# 02_MCU.net
KiCad netlist of a schematic drawn in Altium Designer
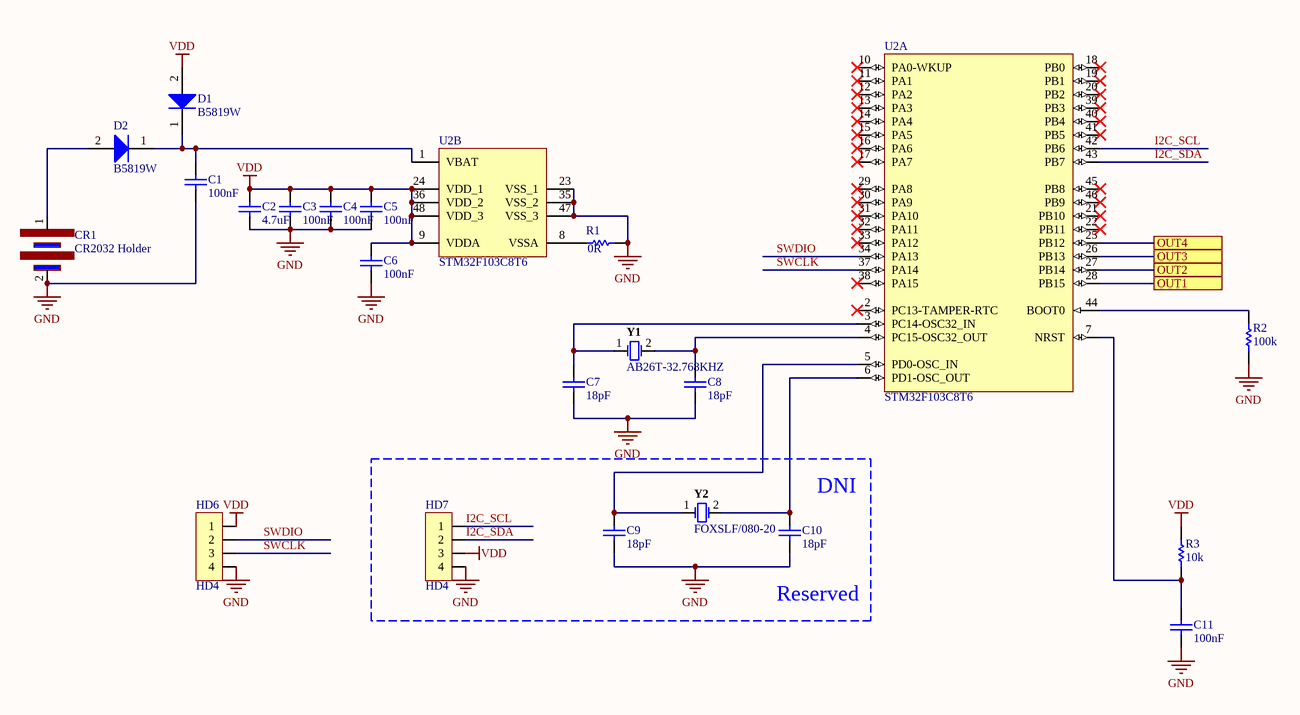
[diagram p0: 02. MCU.SchDoc]

(export (version "E")
  (design (tool "Eeschema 10.0.6"))
  (components
    (comp (ref "C1")
      (value "100nF")
      (footprint "0603 CAP")
      (description "Chip Capacitor, 0.1 uF, +/- 10%, 50 V, -55 to 125 degC, 0603 (1608 Metric), RoHS, Tape and Reel")
      (fields (field (name "TOLERANCE") "10%") (field (name "VOLTAGE") "50V"))
      (libsource (lib "SyTungNguyen") (part "CAP-NP-2"))
    )
    (comp (ref "C2")
      (value "4.7uF")
      (footprint "0603 CAP")
      (description "Chip Capacitor, 0.1 uF, +/- 10%, 50 V, -55 to 125 degC, 0603 (1608 Metric), RoHS, Tape and Reel")
      (fields (field (name "TOLERANCE") "10%") (field (name "VOLTAGE") "50V"))
      (libsource (lib "SyTungNguyen") (part "CAP-NP-2"))
    )
    (comp (ref "C3")
      (value "100nF")
      (footprint "0603 CAP")
      (description "Chip Capacitor, 0.1 uF, +/- 10%, 50 V, -55 to 125 degC, 0603 (1608 Metric), RoHS, Tape and Reel")
      (fields (field (name "TOLERANCE") "10%") (field (name "VOLTAGE") "50V"))
      (libsource (lib "SyTungNguyen") (part "CAP-NP-2"))
    )
    (comp (ref "C4")
      (value "100nF")
      (footprint "0603 CAP")
      (description "Chip Capacitor, 0.1 uF, +/- 10%, 50 V, -55 to 125 degC, 0603 (1608 Metric), RoHS, Tape and Reel")
      (fields (field (name "TOLERANCE") "10%") (field (name "VOLTAGE") "50V"))
      (libsource (lib "SyTungNguyen") (part "CAP-NP-2"))
    )
    (comp (ref "C5")
      (value "100nF")
      (footprint "0603 CAP")
      (description "Chip Capacitor, 0.1 uF, +/- 10%, 50 V, -55 to 125 degC, 0603 (1608 Metric), RoHS, Tape and Reel")
      (fields (field (name "TOLERANCE") "10%") (field (name "VOLTAGE") "50V"))
      (libsource (lib "SyTungNguyen") (part "CAP-NP-2"))
    )
    (comp (ref "C6")
      (value "100nF")
      (footprint "0603 CAP")
      (description "Chip Capacitor, 0.1 uF, +/- 10%, 50 V, -55 to 125 degC, 0603 (1608 Metric), RoHS, Tape and Reel")
      (fields (field (name "TOLERANCE") "10%") (field (name "VOLTAGE") "50V"))
      (libsource (lib "SyTungNguyen") (part "CAP-NP-2"))
    )
    (comp (ref "C7")
      (value "18pF")
      (footprint "0603 CAP")
      (description "Chip Capacitor, 18 pF, +/- 5%, 50 V, -55 to 125 degC, 0603 (1608 Metric), RoHS, Tape and Reel")
      (fields (field (name "MANUFACTURER") "Samsung Electro-Mechanics"))
      (libsource (lib "SyTungNguyen") (part "CAP-NP-2"))
    )
    (comp (ref "C8")
      (value "18pF")
      (footprint "0603 CAP")
      (description "Chip Capacitor, 18 pF, +/- 5%, 50 V, -55 to 125 degC, 0603 (1608 Metric), RoHS, Tape and Reel")
      (fields (field (name "MANUFACTURER") "Samsung Electro-Mechanics"))
      (libsource (lib "SyTungNguyen") (part "CAP-NP-2"))
    )
    (comp (ref "C9")
      (value "18pF")
      (footprint "0603 CAP")
      (description "Chip Capacitor, 18 pF, +/- 5%, 50 V, -55 to 125 degC, 0603 (1608 Metric), RoHS, Tape and Reel")
      (fields (field (name "MANUFACTURER") "Samsung Electro-Mechanics"))
      (libsource (lib "SyTungNguyen") (part "CAP-NP-2"))
    )
    (comp (ref "C10")
      (value "18pF")
      (footprint "0603 CAP")
      (description "Chip Capacitor, 18 pF, +/- 5%, 50 V, -55 to 125 degC, 0603 (1608 Metric), RoHS, Tape and Reel")
      (fields (field (name "MANUFACTURER") "Samsung Electro-Mechanics"))
      (libsource (lib "SyTungNguyen") (part "CAP-NP-2"))
    )
    (comp (ref "C11")
      (value "100nF")
      (footprint "0603 CAP")
      (description "Chip Capacitor, 0.1 uF, +/- 10%, 50 V, -55 to 125 degC, 0603 (1608 Metric), RoHS, Tape and Reel")
      (fields (field (name "TOLERANCE") "10%") (field (name "VOLTAGE") "50V"))
      (libsource (lib "SyTungNguyen") (part "CAP-NP-2"))
    )
    (comp (ref "CR1")
      (value "CR2032 Holder")
      (footprint "CR2032")
      (libsource (lib "SyTungNguyen") (part "CR2032"))
    )
    (comp (ref "D1")
      (value "B5819W")
      (footprint "SOD123")
      (description "Switching Diode, 2-Pin SOD-323, Pb-Free, Tape and Reel")
      (fields (field (name "MANUFACTURER") "On Semiconductor") (field (name "PARTNUMBER") "BAS16HT1G"))
      (libsource (lib "SyTungNguyen") (part "ONSC-D-K1A2-2"))
    )
    (comp (ref "D2")
      (value "B5819W")
      (footprint "SOD123")
      (description "Switching Diode, 2-Pin SOD-323, Pb-Free, Tape and Reel")
      (fields (field (name "MANUFACTURER") "On Semiconductor") (field (name "PARTNUMBER") "BAS16HT1G"))
      (libsource (lib "SyTungNguyen") (part "ONSC-D-K1A2-2"))
    )
    (comp (ref "HD6")
      (value "HD4")
      (footprint "HD4x1 2.54mm")
      (libsource (lib "SyTungNguyen") (part "HD4x1"))
    )
    (comp (ref "HD7")
      (value "HD4")
      (footprint "HD4x1 2.54mm")
      (libsource (lib "SyTungNguyen") (part "HD4x1"))
    )
    (comp (ref "R1")
      (value "0R")
      (footprint "0603 RES")
      (fields (field (name "MANUFACTURER") "Vishay Dale") (field (name "PART NUMBER") "CRCW06030000Z0EB"))
      (libsource (lib "SyTungNguyen") (part "RES"))
    )
    (comp (ref "R2")
      (value "100k")
      (footprint "0603 RES")
      (fields (field (name "MANUFACTURER") "Vishay Dale") (field (name "PART NUMBER") "CRCW06030000Z0EB"))
      (libsource (lib "SyTungNguyen") (part "RES"))
    )
    (comp (ref "R3")
      (value "10k")
      (footprint "0603 RES")
      (fields (field (name "MANUFACTURER") "Vishay Dale") (field (name "PART NUMBER") "CRCW06030000Z0EB"))
      (libsource (lib "SyTungNguyen") (part "RES"))
    )
    (comp (ref "U2")
      (value "STM32F103C8T6")
      (footprint "STM-LQFP48")
      (libsource (lib "SyTungNguyen") (part "MC-ARM-STM32F103X8_B-SQ48"))
    )
    (comp (ref "Y1")
      (value "AB26T-32.768KHZ")
      (footprint "Crystal 3x8")
      (description "Crystal, 12.5 pF, 32.768 KHz, -10 to 60 degC, 2-Pin THD, RoHS, Bulk")
      (fields (field (name "MANUFACTURER") "ABRACON") (field (name "TOLERANCE") "20PPM"))
      (libsource (lib "SyTungNguyen") (part "XTAL-1-2-2"))
    )
    (comp (ref "Y2")
      (value "FOXSLF/080-20")
      (footprint "CRYSTAL HC49")
      (description "Resistance Weld Thru-Hole Crystal, 8 MHz, -20 to 70 degC, 2-Pin THD, RoHS, Bulk")
      (libsource (lib "SyTungNguyen") (part "XTAL-1-2-2"))
    )
  )
  (nets
    (net (code "1") (name "/I2C_SCL") (class "Default")
      (node (ref "HD7") (pin "1") (pinfunction "1_1") (pintype "passive"))
      (node (ref "U2") (pin "42") (pinfunction "PB6_42") (pintype "bidirectional"))
    )
    (net (code "2") (name "/I2C_SDA") (class "Default")
      (node (ref "HD7") (pin "2") (pinfunction "2_2") (pintype "passive"))
      (node (ref "U2") (pin "43") (pinfunction "PB7_43") (pintype "bidirectional"))
    )
    (net (code "3") (name "/OUT1") (class "Default")
      (node (ref "U2") (pin "28") (pinfunction "PB15_28") (pintype "bidirectional"))
    )
    (net (code "4") (name "/OUT2") (class "Default")
      (node (ref "U2") (pin "27") (pinfunction "PB14_27") (pintype "bidirectional"))
    )
    (net (code "5") (name "/OUT3") (class "Default")
      (node (ref "U2") (pin "26") (pinfunction "PB13_26") (pintype "bidirectional"))
    )
    (net (code "6") (name "/OUT4") (class "Default")
      (node (ref "U2") (pin "25") (pinfunction "PB12_25") (pintype "bidirectional"))
    )
    (net (code "7") (name "/SWCLK") (class "Default")
      (node (ref "HD6") (pin "3") (pinfunction "3_3") (pintype "passive"))
      (node (ref "U2") (pin "37") (pinfunction "PA14_37") (pintype "bidirectional"))
    )
    (net (code "8") (name "/SWDIO") (class "Default")
      (node (ref "HD6") (pin "2") (pinfunction "2_2") (pintype "passive"))
      (node (ref "U2") (pin "34") (pinfunction "PA13_34") (pintype "bidirectional"))
    )
    (net (code "9") (name "GND") (class "Default")
      (node (ref "C1") (pin "1") (pinfunction "1_1") (pintype "passive"))
      (node (ref "C10") (pin "1") (pinfunction "1_1") (pintype "passive"))
      (node (ref "C11") (pin "1") (pinfunction "1_1") (pintype "passive"))
      (node (ref "C2") (pin "1") (pinfunction "1_1") (pintype "passive"))
      (node (ref "C3") (pin "1") (pinfunction "1_1") (pintype "passive"))
      (node (ref "C4") (pin "1") (pinfunction "1_1") (pintype "passive"))
      (node (ref "C5") (pin "1") (pinfunction "1_1") (pintype "passive"))
      (node (ref "C6") (pin "1") (pinfunction "1_1") (pintype "passive"))
      (node (ref "C7") (pin "1") (pinfunction "1_1") (pintype "passive"))
      (node (ref "C8") (pin "1") (pinfunction "1_1") (pintype "passive"))
      (node (ref "C9") (pin "1") (pinfunction "1_1") (pintype "passive"))
      (node (ref "CR1") (pin "2") (pinfunction "VSS_2") (pintype "passive"))
      (node (ref "HD6") (pin "4") (pinfunction "4_4") (pintype "passive"))
      (node (ref "HD7") (pin "4") (pinfunction "4_4") (pintype "passive"))
      (node (ref "R1") (pin "2") (pinfunction "2_2") (pintype "passive"))
      (node (ref "R2") (pin "1") (pinfunction "1_1") (pintype "passive"))
      (node (ref "U2") (pin "23") (pinfunction "VSS_1_23") (pintype "power_in"))
      (node (ref "U2") (pin "35") (pinfunction "VSS_2_35") (pintype "power_in"))
      (node (ref "U2") (pin "47") (pinfunction "VSS_3_47") (pintype "power_in"))
    )
    (net (code "10") (name "Net-(CR1-VBAT)") (class "Default")
      (node (ref "CR1") (pin "1") (pinfunction "VBAT_1") (pintype "passive"))
      (node (ref "D2") (pin "2") (pinfunction "A_2") (pintype "passive"))
    )
    (net (code "11") (name "Net-(D1-K)") (class "Default")
      (node (ref "C1") (pin "2") (pinfunction "2_2") (pintype "passive"))
      (node (ref "D1") (pin "1") (pinfunction "K_1") (pintype "passive"))
      (node (ref "D2") (pin "1") (pinfunction "K_1") (pintype "passive"))
      (node (ref "U2") (pin "1") (pinfunction "VBAT_1") (pintype "power_in"))
    )
    (net (code "12") (name "Net-(U2A-BOOT0)") (class "Default")
      (node (ref "R2") (pin "2") (pinfunction "2_2") (pintype "passive"))
      (node (ref "U2") (pin "44") (pinfunction "BOOT0_44") (pintype "input"))
    )
    (net (code "13") (name "Net-(U2A-NRST)") (class "Default")
      (node (ref "C11") (pin "2") (pinfunction "2_2") (pintype "passive"))
      (node (ref "R3") (pin "1") (pinfunction "1_1") (pintype "passive"))
      (node (ref "U2") (pin "7") (pinfunction "NRST_7") (pintype "bidirectional"))
    )
    (net (code "14") (name "Net-(U2A-PC14-OSC32_IN)") (class "Default")
      (node (ref "C7") (pin "2") (pinfunction "2_2") (pintype "passive"))
      (node (ref "U2") (pin "3") (pinfunction "PC14-OSC32_IN_3") (pintype "bidirectional"))
      (node (ref "Y1") (pin "1") (pinfunction "1_1") (pintype "passive"))
    )
    (net (code "15") (name "Net-(U2A-PC15-OSC32_OUT)") (class "Default")
      (node (ref "C8") (pin "2") (pinfunction "2_2") (pintype "passive"))
      (node (ref "U2") (pin "4") (pinfunction "PC15-OSC32_OUT_4") (pintype "bidirectional"))
      (node (ref "Y1") (pin "2") (pinfunction "2_2") (pintype "passive"))
    )
    (net (code "16") (name "Net-(U2A-PD0-OSC_IN)") (class "Default")
      (node (ref "C9") (pin "2") (pinfunction "2_2") (pintype "passive"))
      (node (ref "U2") (pin "5") (pinfunction "PD0-OSC_IN_5") (pintype "bidirectional"))
      (node (ref "Y2") (pin "1") (pinfunction "1_1") (pintype "passive"))
    )
    (net (code "17") (name "Net-(U2A-PD1-OSC_OUT)") (class "Default")
      (node (ref "C10") (pin "2") (pinfunction "2_2") (pintype "passive"))
      (node (ref "U2") (pin "6") (pinfunction "PD1-OSC_OUT_6") (pintype "bidirectional"))
      (node (ref "Y2") (pin "2") (pinfunction "2_2") (pintype "passive"))
    )
    (net (code "18") (name "Net-(U2B-VSSA)") (class "Default")
      (node (ref "R1") (pin "1") (pinfunction "1_1") (pintype "passive"))
      (node (ref "U2") (pin "8") (pinfunction "VSSA_8") (pintype "power_in"))
    )
    (net (code "19") (name "VDD") (class "Default")
      (node (ref "C2") (pin "2") (pinfunction "2_2") (pintype "passive"))
      (node (ref "C3") (pin "2") (pinfunction "2_2") (pintype "passive"))
      (node (ref "C4") (pin "2") (pinfunction "2_2") (pintype "passive"))
      (node (ref "C5") (pin "2") (pinfunction "2_2") (pintype "passive"))
      (node (ref "C6") (pin "2") (pinfunction "2_2") (pintype "passive"))
      (node (ref "D1") (pin "2") (pinfunction "A_2") (pintype "passive"))
      (node (ref "HD6") (pin "1") (pinfunction "1_1") (pintype "passive"))
      (node (ref "HD7") (pin "3") (pinfunction "3_3") (pintype "passive"))
      (node (ref "R3") (pin "2") (pinfunction "2_2") (pintype "passive"))
      (node (ref "U2") (pin "24") (pinfunction "VDD_1_24") (pintype "power_in"))
      (node (ref "U2") (pin "36") (pinfunction "VDD_2_36") (pintype "power_in"))
      (node (ref "U2") (pin "48") (pinfunction "VDD_3_48") (pintype "power_in"))
      (node (ref "U2") (pin "9") (pinfunction "VDDA_9") (pintype "power_in"))
    )
    (net (code "20") (name "unconnected-(U2A-PA0-WKUP-Pad10)") (class "Default")
      (node (ref "U2") (pin "10") (pinfunction "PA0-WKUP_10") (pintype "bidirectional+no_connect"))
    )
    (net (code "21") (name "unconnected-(U2A-PA1-Pad11)") (class "Default")
      (node (ref "U2") (pin "11") (pinfunction "PA1_11") (pintype "bidirectional+no_connect"))
    )
    (net (code "22") (name "unconnected-(U2A-PA2-Pad12)") (class "Default")
      (node (ref "U2") (pin "12") (pinfunction "PA2_12") (pintype "bidirectional+no_connect"))
    )
    (net (code "23") (name "unconnected-(U2A-PA3-Pad13)") (class "Default")
      (node (ref "U2") (pin "13") (pinfunction "PA3_13") (pintype "bidirectional+no_connect"))
    )
    (net (code "24") (name "unconnected-(U2A-PA4-Pad14)") (class "Default")
      (node (ref "U2") (pin "14") (pinfunction "PA4_14") (pintype "bidirectional+no_connect"))
    )
    (net (code "25") (name "unconnected-(U2A-PA5-Pad15)") (class "Default")
      (node (ref "U2") (pin "15") (pinfunction "PA5_15") (pintype "bidirectional+no_connect"))
    )
    (net (code "26") (name "unconnected-(U2A-PA6-Pad16)") (class "Default")
      (node (ref "U2") (pin "16") (pinfunction "PA6_16") (pintype "bidirectional+no_connect"))
    )
    (net (code "27") (name "unconnected-(U2A-PA7-Pad17)") (class "Default")
      (node (ref "U2") (pin "17") (pinfunction "PA7_17") (pintype "bidirectional+no_connect"))
    )
    (net (code "28") (name "unconnected-(U2A-PA8-Pad29)") (class "Default")
      (node (ref "U2") (pin "29") (pinfunction "PA8_29") (pintype "bidirectional+no_connect"))
    )
    (net (code "29") (name "unconnected-(U2A-PA9-Pad30)") (class "Default")
      (node (ref "U2") (pin "30") (pinfunction "PA9_30") (pintype "bidirectional+no_connect"))
    )
    (net (code "30") (name "unconnected-(U2A-PA10-Pad31)") (class "Default")
      (node (ref "U2") (pin "31") (pinfunction "PA10_31") (pintype "bidirectional+no_connect"))
    )
    (net (code "31") (name "unconnected-(U2A-PA11-Pad32)") (class "Default")
      (node (ref "U2") (pin "32") (pinfunction "PA11_32") (pintype "bidirectional+no_connect"))
    )
    (net (code "32") (name "unconnected-(U2A-PA12-Pad33)") (class "Default")
      (node (ref "U2") (pin "33") (pinfunction "PA12_33") (pintype "bidirectional+no_connect"))
    )
    (net (code "33") (name "unconnected-(U2A-PA15-Pad38)") (class "Default")
      (node (ref "U2") (pin "38") (pinfunction "PA15_38") (pintype "bidirectional+no_connect"))
    )
    (net (code "34") (name "unconnected-(U2A-PB0-Pad18)") (class "Default")
      (node (ref "U2") (pin "18") (pinfunction "PB0_18") (pintype "bidirectional+no_connect"))
    )
    (net (code "35") (name "unconnected-(U2A-PB1-Pad19)") (class "Default")
      (node (ref "U2") (pin "19") (pinfunction "PB1_19") (pintype "bidirectional+no_connect"))
    )
    (net (code "36") (name "unconnected-(U2A-PB2-Pad20)") (class "Default")
      (node (ref "U2") (pin "20") (pinfunction "PB2_20") (pintype "bidirectional+no_connect"))
    )
    (net (code "37") (name "unconnected-(U2A-PB3-Pad39)") (class "Default")
      (node (ref "U2") (pin "39") (pinfunction "PB3_39") (pintype "bidirectional+no_connect"))
    )
    (net (code "38") (name "unconnected-(U2A-PB4-Pad40)") (class "Default")
      (node (ref "U2") (pin "40") (pinfunction "PB4_40") (pintype "bidirectional+no_connect"))
    )
    (net (code "39") (name "unconnected-(U2A-PB5-Pad41)") (class "Default")
      (node (ref "U2") (pin "41") (pinfunction "PB5_41") (pintype "bidirectional+no_connect"))
    )
    (net (code "40") (name "unconnected-(U2A-PB8-Pad45)") (class "Default")
      (node (ref "U2") (pin "45") (pinfunction "PB8_45") (pintype "bidirectional+no_connect"))
    )
    (net (code "41") (name "unconnected-(U2A-PB9-Pad46)") (class "Default")
      (node (ref "U2") (pin "46") (pinfunction "PB9_46") (pintype "bidirectional+no_connect"))
    )
    (net (code "42") (name "unconnected-(U2A-PB10-Pad21)") (class "Default")
      (node (ref "U2") (pin "21") (pinfunction "PB10_21") (pintype "bidirectional+no_connect"))
    )
    (net (code "43") (name "unconnected-(U2A-PB11-Pad22)") (class "Default")
      (node (ref "U2") (pin "22") (pinfunction "PB11_22") (pintype "bidirectional+no_connect"))
    )
    (net (code "44") (name "unconnected-(U2A-PC13-TAMPER-RTC-Pad2)") (class "Default")
      (node (ref "U2") (pin "2") (pinfunction "PC13-TAMPER-RTC_2") (pintype "bidirectional+no_connect"))
    )
  )
)
